# power.net
KiCad netlist of a schematic drawn in Altium Designer
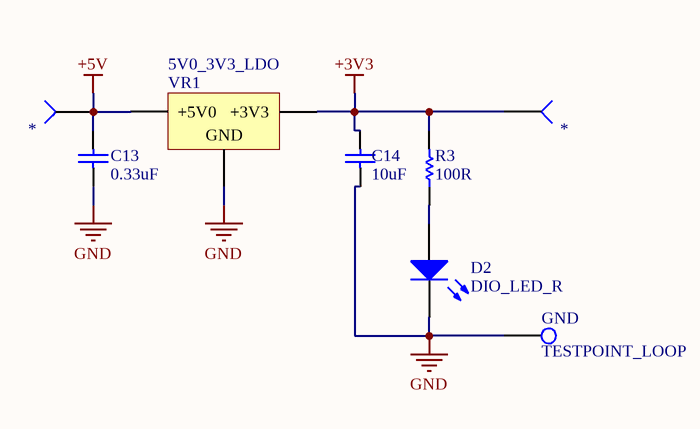
[diagram p0: power.SchDoc]

(export (version "E")
  (design (tool "Eeschema 10.0.6"))
  (components
    (comp (ref "3V3")
      (value "*")
      (footprint "TESTPOINT")
      (description "TESTPOINT_SMD")
      (libsource (lib "UWRT_Schematic_Library_2019") (part "*"))
    )
    (comp (ref "C13")
      (value "0.33uF")
      (footprint "CAPC0603(1608)55_N")
      (description "CAP CER 0.33UF 16V X7R 0603")
      (fields
        (field (name "MANUFACTURER") "Murata Electronics North America")
        (field (name "MPN") "GCM188R71C334KA37D")
      )
      (libsource (lib "UWRT_Schematic_Library_2019") (part "CAP_0.33uF_16V_0603"))
    )
    (comp (ref "C14")
      (value "10uF")
      (footprint "AVX-CAPC3528_V")
      (description "CAP CER 10UF 10V X5R 0603")
      (fields (field (name "MANUFACTURER") "Yageo") (field (name "MPN") "CC0603MRX5R6BB106"))
      (libsource (lib "UWRT_Schematic_Library_2019") (part "CAP_10uF_0603"))
    )
    (comp (ref "D2")
      (value "DIO_LED_R")
      (footprint "LED_0805_LINE")
      (description "LED RED DIFFUSED 0805 SMD")
      (fields (field (name "MANUFACTURER") "OSRAM") (field (name "MPN") "LS R976-NR-1"))
      (libsource (lib "UWRT_Schematic_Library_2019") (part "DIO_LED_R"))
    )
    (comp (ref "GND")
      (value "TESTPOINT_LOOP")
      (footprint "TESTPOINT_LOOP")
      (libsource (lib "UWRT_Schematic_Library_2019") (part "TESTPOINT_LOOP"))
    )
    (comp (ref "R3")
      (value "100R")
      (footprint "RESC0603(1608)_N")
      (description "RES SMD 100 OHM 1% 1/10W 0603")
      (fields (field (name "MANUFACTURER") "Yageo") (field (name "TOLERANCE") "1%"))
      (libsource (lib "UWRT_Schematic_Library_2019") (part "RES_100R_0603"))
    )
    (comp (ref "TESTPOINT_5V")
      (value "*")
      (footprint "TESTPOINT")
      (description "TESTPOINT_SMD")
      (libsource (lib "UWRT_Schematic_Library_2019") (part "*"))
    )
    (comp (ref "VR1")
      (value "5V0_3V3_LDO")
      (footprint "UWRT_Footprint_Library_2019:VOLTAGE_REGULATOR")
      (description "IC REG LINEAR 3.3V 1A DPAK")
      (fields (field (name "MANUFACTURER") "ON Semiconductor") (field (name "MPN") "NCP1117DT33T5G"))
      (libsource (lib "UWRT_Schematic_Library_2019") (part "5V0_3V3_LDO"))
    )
  )
  (nets
    (net (code "1") (name "+3V3") (class "Default")
      (node (ref "3V3") (pin "1") (pinfunction "=value_1") (pintype "passive"))
      (node (ref "C14") (pin "2") (pinfunction "2_2") (pintype "passive"))
      (node (ref "R3") (pin "2") (pinfunction "2_2") (pintype "passive"))
      (node (ref "VR1") (pin "2") (pinfunction "+3V3_2") (pintype "passive"))
    )
    (net (code "2") (name "+5V") (class "Default")
      (node (ref "C13") (pin "2") (pinfunction "2_2") (pintype "passive"))
      (node (ref "TESTPOINT_5V") (pin "1") (pinfunction "=value_1") (pintype "passive"))
      (node (ref "VR1") (pin "3") (pinfunction "+5V0_3") (pintype "passive"))
    )
    (net (code "3") (name "GND") (class "Default")
      (node (ref "C13") (pin "1") (pinfunction "1_1") (pintype "passive"))
      (node (ref "C14") (pin "1") (pinfunction "1_1") (pintype "passive"))
      (node (ref "D2") (pin "2") (pinfunction "K_2") (pintype "passive"))
      (node (ref "GND") (pin "1") (pinfunction "=value_1") (pintype "passive"))
      (node (ref "VR1") (pin "1") (pinfunction "GND_1") (pintype "passive"))
    )
    (net (code "4") (name "Net-(D2-A)") (class "Default")
      (node (ref "D2") (pin "1") (pinfunction "A_1") (pintype "passive"))
      (node (ref "R3") (pin "1") (pinfunction "1_1") (pintype "passive"))
    )
  )
)
